# RMII_Ethernet.net
KiCad netlist of a schematic drawn in Altium Designer
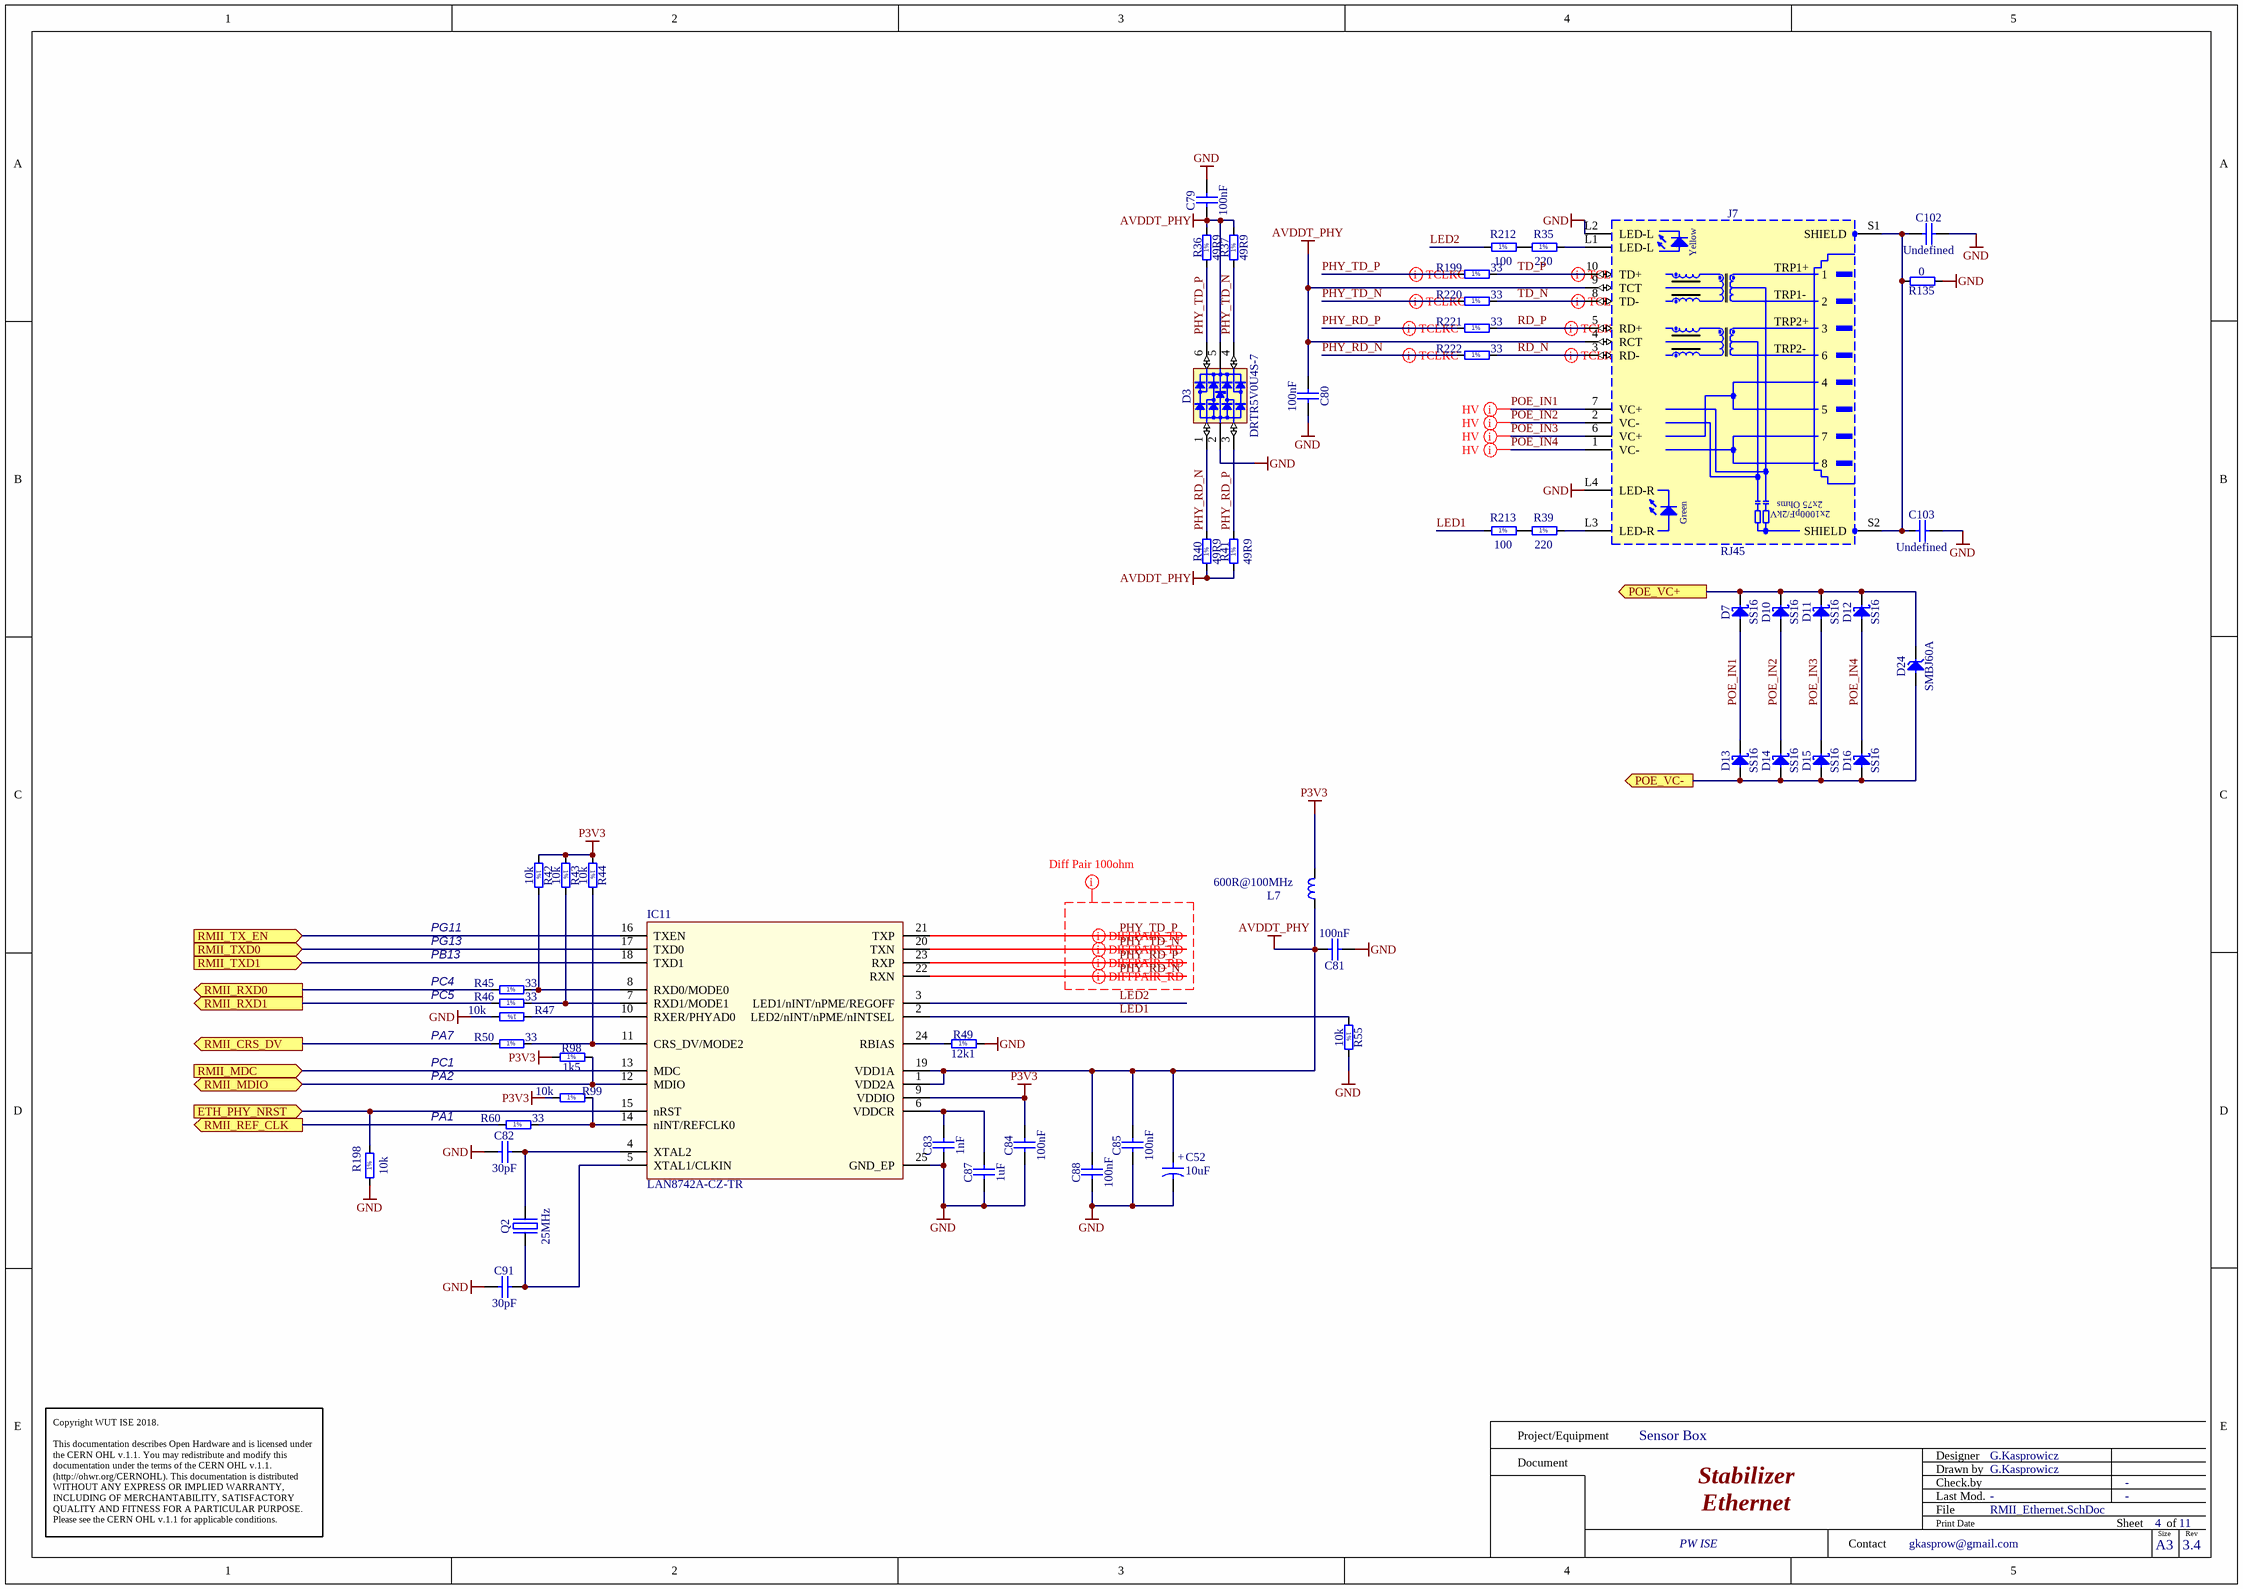
[diagram p0: RMII_Ethernet.SchDoc]

(export (version "E")
  (design (tool "Eeschema 10.0.6"))
  (components
    (comp (ref "C52")
      (value "10uF")
      (footprint "CAPMP3216X180N")
      (description "Polarised capacitor")
      (fields
        (field (name "PART NUMBER") "CTE3216-18_10UF_16V_20%_AVX_TCJ")
        (field (name "VOLTAGE") "16V")
        (field (name "AUTHOR") "CERN DEM JLC")
      )
      (libsource (lib "Capacitors") (part "Capacitor - polarized"))
    )
    (comp (ref "C79")
      (value "100nF")
      (footprint "CAPC1005X55N")
      (description "Non-polarised capacitor")
      (fields
        (field (name "PART NUMBER") "CC0402_100NF_16V_10%_X5R")
        (field (name "VOLTAGE") "16V")
        (field (name "AUTHOR") "CERN DEM JLC")
      )
      (libsource (lib "Capacitors") (part "Capacitor - non polarized"))
    )
    (comp (ref "C80")
      (value "100nF")
      (footprint "CAPC1005X55N")
      (description "Non-polarised capacitor")
      (fields
        (field (name "PART NUMBER") "CC0402_100NF_16V_10%_X5R")
        (field (name "VOLTAGE") "16V")
        (field (name "AUTHOR") "CERN DEM JLC")
      )
      (libsource (lib "Capacitors") (part "Capacitor - non polarized"))
    )
    (comp (ref "C81")
      (value "100nF")
      (footprint "CAPC1005X55N")
      (description "Non-polarised capacitor")
      (fields
        (field (name "PART NUMBER") "CC0402_100NF_16V_10%_X5R")
        (field (name "VOLTAGE") "16V")
        (field (name "AUTHOR") "CERN DEM JLC")
      )
      (libsource (lib "Capacitors") (part "Capacitor - non polarized"))
    )
    (comp (ref "C82")
      (value "30pF")
      (footprint "CAPC1005X55N")
      (description "Non-polarised capacitor")
      (fields
        (field (name "PART NUMBER") "CC0402_30PF_50V_1%_C0G_MURATA_GJM1555C1H300FB01")
        (field (name "VOLTAGE") "50V")
        (field (name "AUTHOR") "CERN DEM BC")
      )
      (libsource (lib "Capacitors") (part "Capacitor - non polarized"))
    )
    (comp (ref "C83")
      (value "1nF")
      (footprint "CAPC1005X55N")
      (description "Non-polarised capacitor")
      (fields
        (field (name "PART NUMBER") "CC0402_1NF_50V_10%_X7R")
        (field (name "VOLTAGE") "50V")
        (field (name "AUTHOR") "CERN DEM JLC")
      )
      (libsource (lib "Capacitors") (part "Capacitor - non polarized"))
    )
    (comp (ref "C84")
      (value "100nF")
      (footprint "CAPC1005X55N")
      (description "Non-polarised capacitor")
      (fields
        (field (name "PART NUMBER") "CC0402_100NF_16V_10%_X5R")
        (field (name "VOLTAGE") "16V")
        (field (name "AUTHOR") "CERN DEM JLC")
      )
      (libsource (lib "Capacitors") (part "Capacitor - non polarized"))
    )
    (comp (ref "C85")
      (value "100nF")
      (footprint "CAPC1005X55N")
      (description "Non-polarised capacitor")
      (fields
        (field (name "PART NUMBER") "CC0402_100NF_16V_10%_X5R")
        (field (name "VOLTAGE") "16V")
        (field (name "AUTHOR") "CERN DEM JLC")
      )
      (libsource (lib "Capacitors") (part "Capacitor - non polarized"))
    )
    (comp (ref "C87")
      (value "1uF")
      (footprint "CAPC1608X87N")
      (description "Non-polarised capacitor")
      (fields
        (field (name "PART NUMBER") "CC0603_1UF_16V_10%_X7R")
        (field (name "VOLTAGE") "16V")
        (field (name "AUTHOR") "CERN DEM JLC")
      )
      (libsource (lib "Capacitors") (part "Capacitor - non polarized"))
    )
    (comp (ref "C88")
      (value "100nF")
      (footprint "CAPC1005X55N")
      (description "Non-polarised capacitor")
      (fields
        (field (name "PART NUMBER") "CC0402_100NF_16V_10%_X5R")
        (field (name "VOLTAGE") "16V")
        (field (name "AUTHOR") "CERN DEM JLC")
      )
      (libsource (lib "Capacitors") (part "Capacitor - non polarized"))
    )
    (comp (ref "C91")
      (value "30pF")
      (footprint "CAPC1005X55N")
      (description "Non-polarised capacitor")
      (fields
        (field (name "PART NUMBER") "CC0402_30PF_50V_1%_C0G_MURATA_GJM1555C1H300FB01")
        (field (name "VOLTAGE") "50V")
        (field (name "AUTHOR") "CERN DEM BC")
      )
      (libsource (lib "Capacitors") (part "Capacitor - non polarized"))
    )
    (comp (ref "C102")
      (value "Undefined")
      (footprint "CAPC2012X135N")
      (description "Non-polarised capacitor")
      (fields (field (name "PART NUMBER") "CC0805_NO-VALUE") (field (name "AUTHOR") "CERN DEM JLC"))
      (libsource (lib "Capacitors") (part "Capacitor - non polarized"))
    )
    (comp (ref "C103")
      (value "Undefined")
      (footprint "CAPC2012X135N")
      (description "Non-polarised capacitor")
      (fields (field (name "PART NUMBER") "CC0805_NO-VALUE") (field (name "AUTHOR") "CERN DEM JLC"))
      (libsource (lib "Capacitors") (part "Capacitor - non polarized"))
    )
    (comp (ref "D3")
      (value "DRTR5V0U4S-7")
      (footprint "SOT65P210X110-6N")
      (description "Integrated Quad Ultra-Low Capacitance ESD Protection")
      (fields (field (name "MANUFACTURER") "DIODES") (field (name "AUTHOR") "GK"))
      (libsource (lib "Diodes") (part "D_TVS_DRTR5V0U4S-7"))
    )
    (comp (ref "D7")
      (value "SS16")
      (footprint "DIOM5127X229N")
      (description "Schottky Diode")
      (fields
        (field (name "VOLTAGE") "60V")
        (field (name "POWER") "1A")
        (field (name "AUTHOR") "CERN DEM JLC")
      )
      (libsource (lib "ICs And Semiconductors") (part "Diode Schottky"))
    )
    (comp (ref "D10")
      (value "SS16")
      (footprint "DIOM5127X229N")
      (description "Schottky Diode")
      (fields
        (field (name "VOLTAGE") "60V")
        (field (name "POWER") "1A")
        (field (name "AUTHOR") "CERN DEM JLC")
      )
      (libsource (lib "ICs And Semiconductors") (part "Diode Schottky"))
    )
    (comp (ref "D11")
      (value "SS16")
      (footprint "DIOM5127X229N")
      (description "Schottky Diode")
      (fields
        (field (name "VOLTAGE") "60V")
        (field (name "POWER") "1A")
        (field (name "AUTHOR") "CERN DEM JLC")
      )
      (libsource (lib "ICs And Semiconductors") (part "Diode Schottky"))
    )
    (comp (ref "D12")
      (value "SS16")
      (footprint "DIOM5127X229N")
      (description "Schottky Diode")
      (fields
        (field (name "VOLTAGE") "60V")
        (field (name "POWER") "1A")
        (field (name "AUTHOR") "CERN DEM JLC")
      )
      (libsource (lib "ICs And Semiconductors") (part "Diode Schottky"))
    )
    (comp (ref "D13")
      (value "SS16")
      (footprint "DIOM5127X229N")
      (description "Schottky Diode")
      (fields
        (field (name "VOLTAGE") "60V")
        (field (name "POWER") "1A")
        (field (name "AUTHOR") "CERN DEM JLC")
      )
      (libsource (lib "ICs And Semiconductors") (part "Diode Schottky"))
    )
    (comp (ref "D14")
      (value "SS16")
      (footprint "DIOM5127X229N")
      (description "Schottky Diode")
      (fields
        (field (name "VOLTAGE") "60V")
        (field (name "POWER") "1A")
        (field (name "AUTHOR") "CERN DEM JLC")
      )
      (libsource (lib "ICs And Semiconductors") (part "Diode Schottky"))
    )
    (comp (ref "D15")
      (value "SS16")
      (footprint "DIOM5127X229N")
      (description "Schottky Diode")
      (fields
        (field (name "VOLTAGE") "60V")
        (field (name "POWER") "1A")
        (field (name "AUTHOR") "CERN DEM JLC")
      )
      (libsource (lib "ICs And Semiconductors") (part "Diode Schottky"))
    )
    (comp (ref "D16")
      (value "SS16")
      (footprint "DIOM5127X229N")
      (description "Schottky Diode")
      (fields
        (field (name "VOLTAGE") "60V")
        (field (name "POWER") "1A")
        (field (name "AUTHOR") "CERN DEM JLC")
      )
      (libsource (lib "ICs And Semiconductors") (part "Diode Schottky"))
    )
    (comp (ref "D24")
      (value "SMBJ60A")
      (footprint "DIOM5336X265N")
      (description "Zener Diode")
      (fields
        (field (name "VOLTAGE") "60V")
        (field (name "POWER") "600W")
        (field (name "AUTHOR") "CERN DEM JLC")
      )
      (libsource (lib "ICs And Semiconductors") (part "Diode Zener"))
    )
    (comp (ref "IC11")
      (value "LAN8742A-CZ-TR")
      (footprint "QFN24_0R5_4X4")
      (libsource (lib "LIBRARY_SCH") (part "IFC_LAN8742A"))
    )
    (comp (ref "J7")
      (value "RJ45")
      (footprint "ABRACON_ARJM11C7-114-BA-EW2")
      (description "MagJack 10/100BaseT, PoE+, 1X1, OG/Y, -40 to 85*C, Tab Up, RoHS")
      (fields
        (field (name "PART NUMBER") "ARJM11C7-114-BA-EW2")
        (field (name "MANUFACTURER") "Abracon")
        (field (name "AUTHOR") "GK")
      )
      (libsource (lib "LIBRARY_SCH") (part "CON_ETH_POE_ARJM11C7"))
    )
    (comp (ref "L7")
      (value "600R@100MHz")
      (footprint "INDC1005X55N")
      (description "Inductor")
      (fields
        (field (name "PART NUMBER") "IND0402_MURATA_BLM15HD601SN1")
        (field (name "POWER") "300mA")
        (field (name "AUTHOR") "CERN DEM JLC")
      )
      (libsource (lib "Inductors & Transformers") (part "Inductor"))
    )
    (comp (ref "Q2")
      (value "25MHz")
      (footprint "XTAL_ABRACON_ABLS")
      (description "Quartz Crystal")
      (fields
        (field (name "PART NUMBER") "XTAL_25MHZ_ABRACON_ABLS-25.000MHZ-B2F-T")
        (field (name "MANUFACTURER") "ABRACON")
        (field (name "AUTHOR") "CERN DEM JLC")
      )
      (libsource (lib "ICs And Semiconductors") (part "Quartz Crystal"))
    )
    (comp (ref "R35")
      (value "220")
      (footprint "RESC1608X55N")
      (description "Resistor - 1%")
      (fields
        (field (name "PART NUMBER") "R0603_220R_1%_0.1W_100PPM")
        (field (name "POWER") "0.1W")
        (field (name "AUTHOR") "CERN DEM JLC")
      )
      (libsource (lib "Resistors") (part "Resistor - 1%"))
    )
    (comp (ref "R36")
      (value "49R9")
      (footprint "RESC1005X40N")
      (description "Resistor - 1%")
      (fields
        (field (name "PART NUMBER") "R0402_49R9_1%_0.0625W_100PPM")
        (field (name "POWER") "0.0625W")
        (field (name "AUTHOR") "CERN DEM JLC")
      )
      (libsource (lib "Resistors") (part "Resistor - 1%"))
    )
    (comp (ref "R37")
      (value "49R9")
      (footprint "RESC1005X40N")
      (description "Resistor - 1%")
      (fields
        (field (name "PART NUMBER") "R0402_49R9_1%_0.0625W_100PPM")
        (field (name "POWER") "0.0625W")
        (field (name "AUTHOR") "CERN DEM JLC")
      )
      (libsource (lib "Resistors") (part "Resistor - 1%"))
    )
    (comp (ref "R39")
      (value "220")
      (footprint "RESC1608X55N")
      (description "Resistor - 1%")
      (fields
        (field (name "PART NUMBER") "R0603_220R_1%_0.1W_100PPM")
        (field (name "POWER") "0.1W")
        (field (name "AUTHOR") "CERN DEM JLC")
      )
      (libsource (lib "Resistors") (part "Resistor - 1%"))
    )
    (comp (ref "R40")
      (value "49R9")
      (footprint "RESC1005X40N")
      (description "Resistor - 1%")
      (fields
        (field (name "PART NUMBER") "R0402_49R9_1%_0.0625W_100PPM")
        (field (name "POWER") "0.0625W")
        (field (name "AUTHOR") "CERN DEM JLC")
      )
      (libsource (lib "Resistors") (part "Resistor - 1%"))
    )
    (comp (ref "R41")
      (value "49R9")
      (footprint "RESC1005X40N")
      (description "Resistor - 1%")
      (fields
        (field (name "PART NUMBER") "R0402_49R9_1%_0.0625W_100PPM")
        (field (name "POWER") "0.0625W")
        (field (name "AUTHOR") "CERN DEM JLC")
      )
      (libsource (lib "Resistors") (part "Resistor - 1%"))
    )
    (comp (ref "R42")
      (value "10k")
      (footprint "RESC1005X40N")
      (description "Resistor - 1%")
      (fields
        (field (name "PART NUMBER") "R0402_10K_1%_0.0625W_100PPM")
        (field (name "POWER") "0.0625W")
        (field (name "AUTHOR") "CERN DEM JLC")
      )
      (libsource (lib "Resistors") (part "Resistor - 1%"))
    )
    (comp (ref "R43")
      (value "10k")
      (footprint "RESC1005X40N")
      (description "Resistor - 1%")
      (fields
        (field (name "PART NUMBER") "R0402_10K_1%_0.0625W_100PPM")
        (field (name "POWER") "0.0625W")
        (field (name "AUTHOR") "CERN DEM JLC")
      )
      (libsource (lib "Resistors") (part "Resistor - 1%"))
    )
    (comp (ref "R44")
      (value "10k")
      (footprint "RESC1005X40N")
      (description "Resistor - 1%")
      (fields
        (field (name "PART NUMBER") "R0402_10K_1%_0.0625W_100PPM")
        (field (name "POWER") "0.0625W")
        (field (name "AUTHOR") "CERN DEM JLC")
      )
      (libsource (lib "Resistors") (part "Resistor - 1%"))
    )
    (comp (ref "R45")
      (value "33")
      (footprint "RESC1005X40N")
      (description "Resistor - 1%")
      (fields
        (field (name "PART NUMBER") "R0402_33R_1%_0.0625W_100PPM")
        (field (name "POWER") "0.0625W")
        (field (name "AUTHOR") "CERN DEM JLC")
      )
      (libsource (lib "Resistors") (part "Resistor - 1%"))
    )
    (comp (ref "R46")
      (value "33")
      (footprint "RESC1005X40N")
      (description "Resistor - 1%")
      (fields
        (field (name "PART NUMBER") "R0402_33R_1%_0.0625W_100PPM")
        (field (name "POWER") "0.0625W")
        (field (name "AUTHOR") "CERN DEM JLC")
      )
      (libsource (lib "Resistors") (part "Resistor - 1%"))
    )
    (comp (ref "R47")
      (value "10k")
      (footprint "RESC1005X40N")
      (description "Resistor - 1%")
      (fields
        (field (name "PART NUMBER") "R0402_10K_1%_0.0625W_100PPM")
        (field (name "POWER") "0.0625W")
        (field (name "AUTHOR") "CERN DEM JLC")
      )
      (libsource (lib "Resistors") (part "Resistor - 1%"))
    )
    (comp (ref "R49")
      (value "12k1")
      (footprint "RESC1005X40N")
      (description "Resistor - 1%")
      (fields
        (field (name "PART NUMBER") "R0402_12K1_1%_0.0625W_100PPM")
        (field (name "POWER") "0.0625W")
        (field (name "AUTHOR") "CERN DEM JLC")
      )
      (libsource (lib "Resistors") (part "Resistor - 1%"))
    )
    (comp (ref "R50")
      (value "33")
      (footprint "RESC1005X40N")
      (description "Resistor - 1%")
      (fields
        (field (name "PART NUMBER") "R0402_33R_1%_0.0625W_100PPM")
        (field (name "POWER") "0.0625W")
        (field (name "AUTHOR") "CERN DEM JLC")
      )
      (libsource (lib "Resistors") (part "Resistor - 1%"))
    )
    (comp (ref "R55")
      (value "10k")
      (footprint "RESC1005X40N")
      (description "Resistor - 1%")
      (fields
        (field (name "PART NUMBER") "R0402_10K_1%_0.0625W_100PPM")
        (field (name "POWER") "0.0625W")
        (field (name "AUTHOR") "CERN DEM JLC")
      )
      (libsource (lib "Resistors") (part "Resistor - 1%"))
    )
    (comp (ref "R60")
      (value "33")
      (footprint "RESC1005X40N")
      (description "Resistor - 1%")
      (fields
        (field (name "PART NUMBER") "R0402_33R_1%_0.0625W_100PPM")
        (field (name "POWER") "0.0625W")
        (field (name "AUTHOR") "CERN DEM JLC")
      )
      (libsource (lib "Resistors") (part "Resistor - 1%"))
    )
    (comp (ref "R98")
      (value "1k5")
      (footprint "RESC1005X40N")
      (description "Resistor - 1%")
      (fields
        (field (name "PART NUMBER") "R0402_1K5_1%_0.0625W_100PPM")
        (field (name "POWER") "0.0625W")
        (field (name "AUTHOR") "CERN DEM JLC")
      )
      (libsource (lib "Resistors") (part "Resistor - 1%"))
    )
    (comp (ref "R99")
      (value "10k")
      (footprint "RESC1005X40N")
      (description "Resistor - 1%")
      (fields
        (field (name "PART NUMBER") "R0402_10K_1%_0.0625W_100PPM")
        (field (name "POWER") "0.0625W")
        (field (name "AUTHOR") "CERN DEM JLC")
      )
      (libsource (lib "Resistors") (part "Resistor - 1%"))
    )
    (comp (ref "R135")
      (value "0")
      (footprint "RESC1608X55N")
      (description "Resistor")
      (fields
        (field (name "PART NUMBER") "R0603_0R_JUMPER")
        (field (name "MANUFACTURER") "GENERIC")
        (field (name "AUTHOR") "CERN DEM JLC")
      )
      (libsource (lib "Resistors") (part "Resistor"))
    )
    (comp (ref "R198")
      (value "10k")
      (footprint "RESC1005X40N")
      (description "Resistor - 1%")
      (fields
        (field (name "PART NUMBER") "R0402_10K_1%_0.0625W_100PPM")
        (field (name "POWER") "0.0625W")
        (field (name "AUTHOR") "CERN DEM JLC")
      )
      (libsource (lib "Resistors") (part "Resistor - 1%"))
    )
    (comp (ref "R199")
      (value "33")
      (footprint "RESC1005X40N")
      (description "Resistor - 1%")
      (fields
        (field (name "PART NUMBER") "R0402_33R_1%_0.0625W_100PPM")
        (field (name "POWER") "0.0625W")
        (field (name "AUTHOR") "CERN DEM JLC")
      )
      (libsource (lib "Resistors") (part "Resistor - 1%"))
    )
    (comp (ref "R212")
      (value "100")
      (footprint "RESC1005X40N")
      (description "Resistor - 1%")
      (fields
        (field (name "PART NUMBER") "R0402_100R_1%_0.0625W_100PPM")
        (field (name "POWER") "0.0625W")
        (field (name "AUTHOR") "CERN DEM JLC")
      )
      (libsource (lib "Resistors") (part "Resistor - 1%"))
    )
    (comp (ref "R213")
      (value "100")
      (footprint "RESC1005X40N")
      (description "Resistor - 1%")
      (fields
        (field (name "PART NUMBER") "R0402_100R_1%_0.0625W_100PPM")
        (field (name "POWER") "0.0625W")
        (field (name "AUTHOR") "CERN DEM JLC")
      )
      (libsource (lib "Resistors") (part "Resistor - 1%"))
    )
    (comp (ref "R220")
      (value "33")
      (footprint "RESC1005X40N")
      (description "Resistor - 1%")
      (fields
        (field (name "PART NUMBER") "R0402_33R_1%_0.0625W_100PPM")
        (field (name "POWER") "0.0625W")
        (field (name "AUTHOR") "CERN DEM JLC")
      )
      (libsource (lib "Resistors") (part "Resistor - 1%"))
    )
    (comp (ref "R221")
      (value "33")
      (footprint "RESC1005X40N")
      (description "Resistor - 1%")
      (fields
        (field (name "PART NUMBER") "R0402_33R_1%_0.0625W_100PPM")
        (field (name "POWER") "0.0625W")
        (field (name "AUTHOR") "CERN DEM JLC")
      )
      (libsource (lib "Resistors") (part "Resistor - 1%"))
    )
    (comp (ref "R222")
      (value "33")
      (footprint "RESC1005X40N")
      (description "Resistor - 1%")
      (fields
        (field (name "PART NUMBER") "R0402_33R_1%_0.0625W_100PPM")
        (field (name "POWER") "0.0625W")
        (field (name "AUTHOR") "CERN DEM JLC")
      )
      (libsource (lib "Resistors") (part "Resistor - 1%"))
    )
  )
  (nets
    (net (code "1") (name "/ETH_PHY_NRST") (class "Default")
      (node (ref "IC11") (pin "15") (pinfunction "nRST_15") (pintype "passive"))
      (node (ref "R198") (pin "2") (pinfunction "2_2") (pintype "passive"))
    )
    (net (code "2") (name "/LED1") (class "Default")
      (node (ref "IC11") (pin "2") (pinfunction "LED2/nINT/nPME/nINTSEL_2") (pintype "passive"))
      (node (ref "R213") (pin "1") (pinfunction "1_1") (pintype "passive"))
      (node (ref "R55") (pin "1") (pinfunction "1_1") (pintype "passive"))
    )
    (net (code "3") (name "/LED2") (class "Default")
      (node (ref "IC11") (pin "3") (pinfunction "LED1/nINT/nPME/REGOFF_3") (pintype "passive"))
      (node (ref "R212") (pin "1") (pinfunction "1_1") (pintype "passive"))
    )
    (net (code "4") (name "/PHY_RD_N") (class "Default")
      (node (ref "D3") (pin "1") (pinfunction "I/O1_1") (pintype "bidirectional"))
      (node (ref "IC11") (pin "22") (pinfunction "RXN_22") (pintype "passive"))
      (node (ref "R222") (pin "1") (pinfunction "1_1") (pintype "passive"))
      (node (ref "R40") (pin "2") (pinfunction "2_2") (pintype "passive"))
    )
    (net (code "5") (name "/PHY_RD_P") (class "Default")
      (node (ref "D3") (pin "3") (pinfunction "I/O2_3") (pintype "bidirectional"))
      (node (ref "IC11") (pin "23") (pinfunction "RXP_23") (pintype "passive"))
      (node (ref "R221") (pin "1") (pinfunction "1_1") (pintype "passive"))
      (node (ref "R41") (pin "2") (pinfunction "2_2") (pintype "passive"))
    )
    (net (code "6") (name "/PHY_TD_N") (class "Default")
      (node (ref "D3") (pin "4") (pinfunction "I/O3_4") (pintype "bidirectional"))
      (node (ref "IC11") (pin "20") (pinfunction "TXN_20") (pintype "passive"))
      (node (ref "R220") (pin "1") (pinfunction "1_1") (pintype "passive"))
      (node (ref "R37") (pin "1") (pinfunction "1_1") (pintype "passive"))
    )
    (net (code "7") (name "/PHY_TD_P") (class "Default")
      (node (ref "D3") (pin "6") (pinfunction "I/O4_6") (pintype "bidirectional"))
      (node (ref "IC11") (pin "21") (pinfunction "TXP_21") (pintype "passive"))
      (node (ref "R199") (pin "1") (pinfunction "1_1") (pintype "passive"))
      (node (ref "R36") (pin "1") (pinfunction "1_1") (pintype "passive"))
    )
    (net (code "8") (name "/POE_IN1") (class "Default")
      (node (ref "D13") (pin "1") (pinfunction "C_1") (pintype "passive"))
      (node (ref "D7") (pin "2") (pinfunction "A_2") (pintype "passive"))
      (node (ref "J7") (pin "7") (pinfunction "VC+_7") (pintype "passive"))
    )
    (net (code "9") (name "/POE_IN2") (class "Default")
      (node (ref "D10") (pin "2") (pinfunction "A_2") (pintype "passive"))
      (node (ref "D14") (pin "1") (pinfunction "C_1") (pintype "passive"))
      (node (ref "J7") (pin "2") (pinfunction "VC-_2") (pintype "passive"))
    )
    (net (code "10") (name "/POE_IN3") (class "Default")
      (node (ref "D11") (pin "2") (pinfunction "A_2") (pintype "passive"))
      (node (ref "D15") (pin "1") (pinfunction "C_1") (pintype "passive"))
      (node (ref "J7") (pin "6") (pinfunction "VC+_6") (pintype "passive"))
    )
    (net (code "11") (name "/POE_IN4") (class "Default")
      (node (ref "D12") (pin "2") (pinfunction "A_2") (pintype "passive"))
      (node (ref "D16") (pin "1") (pinfunction "C_1") (pintype "passive"))
      (node (ref "J7") (pin "1") (pinfunction "VC-_1") (pintype "passive"))
    )
    (net (code "12") (name "/POE_VC+") (class "Default")
      (node (ref "D10") (pin "1") (pinfunction "C_1") (pintype "passive"))
      (node (ref "D11") (pin "1") (pinfunction "C_1") (pintype "passive"))
      (node (ref "D12") (pin "1") (pinfunction "C_1") (pintype "passive"))
      (node (ref "D24") (pin "1") (pinfunction "C_1") (pintype "passive"))
      (node (ref "D7") (pin "1") (pinfunction "C_1") (pintype "passive"))
    )
    (net (code "13") (name "/POE_VC-") (class "Default")
      (node (ref "D13") (pin "2") (pinfunction "A_2") (pintype "passive"))
      (node (ref "D14") (pin "2") (pinfunction "A_2") (pintype "passive"))
      (node (ref "D15") (pin "2") (pinfunction "A_2") (pintype "passive"))
      (node (ref "D16") (pin "2") (pinfunction "A_2") (pintype "passive"))
      (node (ref "D24") (pin "2") (pinfunction "A_2") (pintype "passive"))
    )
    (net (code "14") (name "/RD_N") (class "Default")
      (node (ref "J7") (pin "3") (pinfunction "RD-_3") (pintype "bidirectional"))
      (node (ref "R222") (pin "2") (pinfunction "2_2") (pintype "passive"))
    )
    (net (code "15") (name "/RD_P") (class "Default")
      (node (ref "J7") (pin "5") (pinfunction "RD+_5") (pintype "bidirectional"))
      (node (ref "R221") (pin "2") (pinfunction "2_2") (pintype "passive"))
    )
    (net (code "16") (name "/RMII_CRS_DV") (class "Default")
      (node (ref "R50") (pin "1") (pinfunction "1_1") (pintype "passive"))
    )
    (net (code "17") (name "/RMII_MDC") (class "Default")
      (node (ref "IC11") (pin "13") (pinfunction "MDC_13") (pintype "passive"))
    )
    (net (code "18") (name "/RMII_MDIO") (class "Default")
      (node (ref "IC11") (pin "12") (pinfunction "MDIO_12") (pintype "passive"))
      (node (ref "R98") (pin "2") (pinfunction "2_2") (pintype "passive"))
    )
    (net (code "19") (name "/RMII_REF_CLK") (class "Default")
      (node (ref "R60") (pin "1") (pinfunction "1_1") (pintype "passive"))
    )
    (net (code "20") (name "/RMII_RXD0") (class "Default")
      (node (ref "R45") (pin "1") (pinfunction "1_1") (pintype "passive"))
    )
    (net (code "21") (name "/RMII_RXD1") (class "Default")
      (node (ref "R46") (pin "1") (pinfunction "1_1") (pintype "passive"))
    )
    (net (code "22") (name "/RMII_TXD0") (class "Default")
      (node (ref "IC11") (pin "17") (pinfunction "TXD0_17") (pintype "passive"))
    )
    (net (code "23") (name "/RMII_TXD1") (class "Default")
      (node (ref "IC11") (pin "18") (pinfunction "TXD1_18") (pintype "passive"))
    )
    (net (code "24") (name "/RMII_TX_EN") (class "Default")
      (node (ref "IC11") (pin "16") (pinfunction "TXEN_16") (pintype "passive"))
    )
    (net (code "25") (name "/TD_N") (class "Default")
      (node (ref "J7") (pin "8") (pinfunction "TD-_8") (pintype "bidirectional"))
      (node (ref "R220") (pin "2") (pinfunction "2_2") (pintype "passive"))
    )
    (net (code "26") (name "/TD_P") (class "Default")
      (node (ref "J7") (pin "10") (pinfunction "TD+_10") (pintype "bidirectional"))
      (node (ref "R199") (pin "2") (pinfunction "2_2") (pintype "passive"))
    )
    (net (code "27") (name "AVDDT_PHY") (class "Default")
      (node (ref "C52") (pin "1") (pinfunction "1_1") (pintype "passive"))
      (node (ref "C79") (pin "1") (pinfunction "1_1") (pintype "passive"))
      (node (ref "C80") (pin "2") (pinfunction "2_2") (pintype "passive"))
      (node (ref "C81") (pin "2") (pinfunction "2_2") (pintype "passive"))
      (node (ref "C85") (pin "2") (pinfunction "2_2") (pintype "passive"))
      (node (ref "C88") (pin "2") (pinfunction "2_2") (pintype "passive"))
      (node (ref "D3") (pin "5") (pinfunction "VBUS_5") (pintype "power_in"))
      (node (ref "IC11") (pin "1") (pinfunction "VDD2A_1") (pintype "passive"))
      (node (ref "IC11") (pin "19") (pinfunction "VDD1A_19") (pintype "passive"))
      (node (ref "J7") (pin "4") (pinfunction "RCT_4") (pintype "bidirectional"))
      (node (ref "J7") (pin "9") (pinfunction "TCT_9") (pintype "bidirectional"))
      (node (ref "L7") (pin "1") (pinfunction "1_1") (pintype "passive"))
      (node (ref "R36") (pin "2") (pinfunction "2_2") (pintype "passive"))
      (node (ref "R37") (pin "2") (pinfunction "2_2") (pintype "passive"))
      (node (ref "R40") (pin "1") (pinfunction "1_1") (pintype "passive"))
      (node (ref "R41") (pin "1") (pinfunction "1_1") (pintype "passive"))
    )
    (net (code "28") (name "GND") (class "Default")
      (node (ref "C102") (pin "2") (pinfunction "2_2") (pintype "passive"))
      (node (ref "C103") (pin "2") (pinfunction "2_2") (pintype "passive"))
      (node (ref "C52") (pin "2") (pinfunction "2_2") (pintype "passive"))
      (node (ref "C79") (pin "2") (pinfunction "2_2") (pintype "passive"))
      (node (ref "C80") (pin "1") (pinfunction "1_1") (pintype "passive"))
      (node (ref "C81") (pin "1") (pinfunction "1_1") (pintype "passive"))
      (node (ref "C82") (pin "1") (pinfunction "1_1") (pintype "passive"))
      (node (ref "C83") (pin "1") (pinfunction "1_1") (pintype "passive"))
      (node (ref "C84") (pin "1") (pinfunction "1_1") (pintype "passive"))
      (node (ref "C85") (pin "1") (pinfunction "1_1") (pintype "passive"))
      (node (ref "C87") (pin "1") (pinfunction "1_1") (pintype "passive"))
      (node (ref "C88") (pin "1") (pinfunction "1_1") (pintype "passive"))
      (node (ref "C91") (pin "1") (pinfunction "1_1") (pintype "passive"))
      (node (ref "D3") (pin "2") (pinfunction "GND_2") (pintype "power_in"))
      (node (ref "IC11") (pin "25") (pinfunction "GND_EP_25") (pintype "passive"))
      (node (ref "J7") (pin "L2") (pinfunction "LED-L_L2") (pintype "passive"))
      (node (ref "J7") (pin "L4") (pinfunction "LED-R_L4") (pintype "passive"))
      (node (ref "R135") (pin "1") (pinfunction "1_1") (pintype "passive"))
      (node (ref "R198") (pin "1") (pinfunction "1_1") (pintype "passive"))
      (node (ref "R47") (pin "2") (pinfunction "2_2") (pintype "passive"))
      (node (ref "R49") (pin "2") (pinfunction "2_2") (pintype "passive"))
      (node (ref "R55") (pin "2") (pinfunction "2_2") (pintype "passive"))
    )
    (net (code "29") (name "Net-(C102-Pad1)") (class "Default")
      (node (ref "C102") (pin "1") (pinfunction "1_1") (pintype "passive"))
      (node (ref "C103") (pin "1") (pinfunction "1_1") (pintype "passive"))
      (node (ref "J7") (pin "S1") (pinfunction "SHIELD_S1") (pintype "power_in"))
      (node (ref "J7") (pin "S2") (pinfunction "SHIELD_S2") (pintype "power_in"))
      (node (ref "R135") (pin "2") (pinfunction "2_2") (pintype "passive"))
    )
    (net (code "30") (name "Net-(IC11-CRS_DV{slash}MODE2)") (class "Default")
      (node (ref "IC11") (pin "11") (pinfunction "CRS_DV/MODE2_11") (pintype "passive"))
      (node (ref "R44") (pin "2") (pinfunction "2_2") (pintype "passive"))
      (node (ref "R50") (pin "2") (pinfunction "2_2") (pintype "passive"))
    )
    (net (code "31") (name "Net-(IC11-RBIAS)") (class "Default")
      (node (ref "IC11") (pin "24") (pinfunction "RBIAS_24") (pintype "passive"))
      (node (ref "R49") (pin "1") (pinfunction "1_1") (pintype "passive"))
    )
    (net (code "32") (name "Net-(IC11-RXD0{slash}MODE0)") (class "Default")
      (node (ref "IC11") (pin "8") (pinfunction "RXD0/MODE0_8") (pintype "passive"))
      (node (ref "R42") (pin "2") (pinfunction "2_2") (pintype "passive"))
      (node (ref "R45") (pin "2") (pinfunction "2_2") (pintype "passive"))
    )
    (net (code "33") (name "Net-(IC11-RXD1{slash}MODE1)") (class "Default")
      (node (ref "IC11") (pin "7") (pinfunction "RXD1/MODE1_7") (pintype "passive"))
      (node (ref "R43") (pin "2") (pinfunction "2_2") (pintype "passive"))
      (node (ref "R46") (pin "2") (pinfunction "2_2") (pintype "passive"))
    )
    (net (code "34") (name "Net-(IC11-RXER{slash}PHYAD0)") (class "Default")
      (node (ref "IC11") (pin "10") (pinfunction "RXER/PHYAD0_10") (pintype "passive"))
      (node (ref "R47") (pin "1") (pinfunction "1_1") (pintype "passive"))
    )
    (net (code "35") (name "Net-(IC11-VDDCR)") (class "Default")
      (node (ref "C83") (pin "2") (pinfunction "2_2") (pintype "passive"))
      (node (ref "C87") (pin "2") (pinfunction "2_2") (pintype "passive"))
      (node (ref "IC11") (pin "6") (pinfunction "VDDCR_6") (pintype "passive"))
    )
    (net (code "36") (name "Net-(IC11-XTAL1{slash}CLKIN)") (class "Default")
      (node (ref "C91") (pin "2") (pinfunction "2_2") (pintype "passive"))
      (node (ref "IC11") (pin "5") (pinfunction "XTAL1/CLKIN_5") (pintype "passive"))
      (node (ref "Q2") (pin "1") (pinfunction "OSC1_1") (pintype "passive"))
    )
    (net (code "37") (name "Net-(IC11-XTAL2)") (class "Default")
      (node (ref "C82") (pin "2") (pinfunction "2_2") (pintype "passive"))
      (node (ref "IC11") (pin "4") (pinfunction "XTAL2_4") (pintype "passive"))
      (node (ref "Q2") (pin "2") (pinfunction "OSC2_2") (pintype "passive"))
    )
    (net (code "38") (name "Net-(IC11-nINT{slash}REFCLK0)") (class "Default")
      (node (ref "IC11") (pin "14") (pinfunction "nINT/REFCLK0_14") (pintype "passive"))
      (node (ref "R60") (pin "2") (pinfunction "2_2") (pintype "passive"))
      (node (ref "R99") (pin "2") (pinfunction "2_2") (pintype "passive"))
    )
    (net (code "39") (name "Net-(J7-LED-L-PadL1)") (class "Default")
      (node (ref "J7") (pin "L1") (pinfunction "LED-L_L1") (pintype "passive"))
      (node (ref "R35") (pin "2") (pinfunction "2_2") (pintype "passive"))
    )
    (net (code "40") (name "Net-(J7-LED-R-PadL3)") (class "Default")
      (node (ref "J7") (pin "L3") (pinfunction "LED-R_L3") (pintype "passive"))
      (node (ref "R39") (pin "2") (pinfunction "2_2") (pintype "passive"))
    )
    (net (code "41") (name "Net-(R212-Pad2)") (class "Default")
      (node (ref "R212") (pin "2") (pinfunction "2_2") (pintype "passive"))
      (node (ref "R35") (pin "1") (pinfunction "1_1") (pintype "passive"))
    )
    (net (code "42") (name "Net-(R213-Pad2)") (class "Default")
      (node (ref "R213") (pin "2") (pinfunction "2_2") (pintype "passive"))
      (node (ref "R39") (pin "1") (pinfunction "1_1") (pintype "passive"))
    )
    (net (code "43") (name "P3V3") (class "Default")
      (node (ref "C84") (pin "2") (pinfunction "2_2") (pintype "passive"))
      (node (ref "IC11") (pin "9") (pinfunction "VDDIO_9") (pintype "passive"))
      (node (ref "L7") (pin "2") (pinfunction "2_2") (pintype "passive"))
      (node (ref "R42") (pin "1") (pinfunction "1_1") (pintype "passive"))
      (node (ref "R43") (pin "1") (pinfunction "1_1") (pintype "passive"))
      (node (ref "R44") (pin "1") (pinfunction "1_1") (pintype "passive"))
      (node (ref "R98") (pin "1") (pinfunction "1_1") (pintype "passive"))
      (node (ref "R99") (pin "1") (pinfunction "1_1") (pintype "passive"))
    )
  )
)
